# TK510_Kontakter.net
KiCad netlist of a schematic drawn in Altium Designer
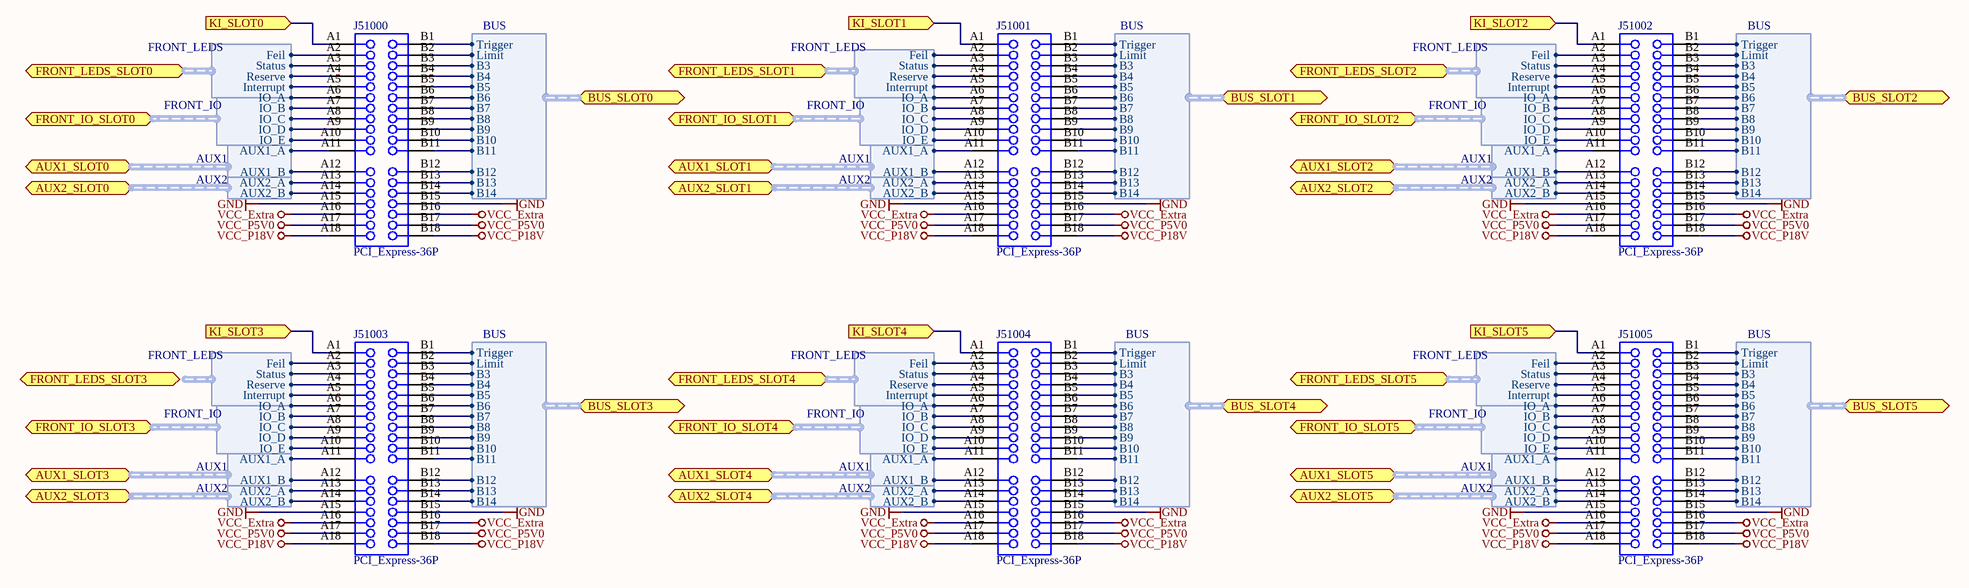
[diagram p0: TK510_Kontakter.SchDoc]

(export (version "E")
  (design (tool "Eeschema 10.0.6"))
  (components
    (comp (ref "J51000")
      (value "PCI_Express-36P")
      (footprint "PCI_Express-36P")
      (description "Board-to-Board Connector, PTH, Vertical, Pitch 1.00mm, 36-Position")
      (libsource (lib "OVLib") (part "PCI_Express-36P"))
    )
    (comp (ref "J51001")
      (value "PCI_Express-36P")
      (footprint "PCI_Express-36P")
      (description "Board-to-Board Connector, PTH, Vertical, Pitch 1.00mm, 36-Position")
      (libsource (lib "OVLib") (part "PCI_Express-36P"))
    )
    (comp (ref "J51002")
      (value "PCI_Express-36P")
      (footprint "PCI_Express-36P")
      (description "Board-to-Board Connector, PTH, Vertical, Pitch 1.00mm, 36-Position")
      (libsource (lib "OVLib") (part "PCI_Express-36P"))
    )
    (comp (ref "J51003")
      (value "PCI_Express-36P")
      (footprint "PCI_Express-36P")
      (description "Board-to-Board Connector, PTH, Vertical, Pitch 1.00mm, 36-Position")
      (libsource (lib "OVLib") (part "PCI_Express-36P"))
    )
    (comp (ref "J51004")
      (value "PCI_Express-36P")
      (footprint "PCI_Express-36P")
      (description "Board-to-Board Connector, PTH, Vertical, Pitch 1.00mm, 36-Position")
      (libsource (lib "OVLib") (part "PCI_Express-36P"))
    )
    (comp (ref "J51005")
      (value "PCI_Express-36P")
      (footprint "PCI_Express-36P")
      (description "Board-to-Board Connector, PTH, Vertical, Pitch 1.00mm, 36-Position")
      (libsource (lib "OVLib") (part "PCI_Express-36P"))
    )
  )
  (nets
    (net (code "21") (name "/KI_SLOT0") (class "Default")
      (node (ref "J51000") (pin "A1") (pinfunction "A1_A1") (pintype "passive"))
    )
    (net (code "22") (name "/KI_SLOT1") (class "Default")
      (node (ref "J51001") (pin "A1") (pinfunction "A1_A1") (pintype "passive"))
    )
    (net (code "23") (name "/KI_SLOT2") (class "Default")
      (node (ref "J51002") (pin "A1") (pinfunction "A1_A1") (pintype "passive"))
    )
    (net (code "24") (name "/KI_SLOT3") (class "Default")
      (node (ref "J51003") (pin "A1") (pinfunction "A1_A1") (pintype "passive"))
    )
    (net (code "25") (name "/KI_SLOT4") (class "Default")
      (node (ref "J51004") (pin "A1") (pinfunction "A1_A1") (pintype "passive"))
    )
    (net (code "26") (name "/KI_SLOT5") (class "Default")
      (node (ref "J51005") (pin "A1") (pinfunction "A1_A1") (pintype "passive"))
    )
    (net (code "29") (name "GND") (class "Default")
      (node (ref "J51000") (pin "A15") (pinfunction "A15_A15") (pintype "passive"))
      (node (ref "J51000") (pin "B15") (pinfunction "B15_B15") (pintype "passive"))
      (node (ref "J51001") (pin "A15") (pinfunction "A15_A15") (pintype "passive"))
      (node (ref "J51001") (pin "B15") (pinfunction "B15_B15") (pintype "passive"))
      (node (ref "J51002") (pin "A15") (pinfunction "A15_A15") (pintype "passive"))
      (node (ref "J51002") (pin "B15") (pinfunction "B15_B15") (pintype "passive"))
      (node (ref "J51003") (pin "A15") (pinfunction "A15_A15") (pintype "passive"))
      (node (ref "J51003") (pin "B15") (pinfunction "B15_B15") (pintype "passive"))
      (node (ref "J51004") (pin "A15") (pinfunction "A15_A15") (pintype "passive"))
      (node (ref "J51004") (pin "B15") (pinfunction "B15_B15") (pintype "passive"))
      (node (ref "J51005") (pin "A15") (pinfunction "A15_A15") (pintype "passive"))
      (node (ref "J51005") (pin "B15") (pinfunction "B15_B15") (pintype "passive"))
    )
    (net (code "30") (name "VCC_Extra") (class "Default")
      (node (ref "J51000") (pin "A16") (pinfunction "A16_A16") (pintype "passive"))
      (node (ref "J51000") (pin "B16") (pinfunction "B16_B16") (pintype "passive"))
      (node (ref "J51001") (pin "A16") (pinfunction "A16_A16") (pintype "passive"))
      (node (ref "J51001") (pin "B16") (pinfunction "B16_B16") (pintype "passive"))
      (node (ref "J51002") (pin "A16") (pinfunction "A16_A16") (pintype "passive"))
      (node (ref "J51002") (pin "B16") (pinfunction "B16_B16") (pintype "passive"))
      (node (ref "J51003") (pin "A16") (pinfunction "A16_A16") (pintype "passive"))
      (node (ref "J51003") (pin "B16") (pinfunction "B16_B16") (pintype "passive"))
      (node (ref "J51004") (pin "A16") (pinfunction "A16_A16") (pintype "passive"))
      (node (ref "J51004") (pin "B16") (pinfunction "B16_B16") (pintype "passive"))
      (node (ref "J51005") (pin "A16") (pinfunction "A16_A16") (pintype "passive"))
      (node (ref "J51005") (pin "B16") (pinfunction "B16_B16") (pintype "passive"))
    )
    (net (code "31") (name "VCC_P5V0") (class "Default")
      (node (ref "J51000") (pin "A17") (pinfunction "A17_A17") (pintype "passive"))
      (node (ref "J51000") (pin "B17") (pinfunction "B17_B17") (pintype "passive"))
      (node (ref "J51001") (pin "A17") (pinfunction "A17_A17") (pintype "passive"))
      (node (ref "J51001") (pin "B17") (pinfunction "B17_B17") (pintype "passive"))
      (node (ref "J51002") (pin "A17") (pinfunction "A17_A17") (pintype "passive"))
      (node (ref "J51002") (pin "B17") (pinfunction "B17_B17") (pintype "passive"))
      (node (ref "J51003") (pin "A17") (pinfunction "A17_A17") (pintype "passive"))
      (node (ref "J51003") (pin "B17") (pinfunction "B17_B17") (pintype "passive"))
      (node (ref "J51004") (pin "A17") (pinfunction "A17_A17") (pintype "passive"))
      (node (ref "J51004") (pin "B17") (pinfunction "B17_B17") (pintype "passive"))
      (node (ref "J51005") (pin "A17") (pinfunction "A17_A17") (pintype "passive"))
      (node (ref "J51005") (pin "B17") (pinfunction "B17_B17") (pintype "passive"))
    )
    (net (code "32") (name "VCC_P18V") (class "Default")
      (node (ref "J51000") (pin "A18") (pinfunction "A18_A18") (pintype "passive"))
      (node (ref "J51000") (pin "B18") (pinfunction "B18_B18") (pintype "passive"))
      (node (ref "J51001") (pin "A18") (pinfunction "A18_A18") (pintype "passive"))
      (node (ref "J51001") (pin "B18") (pinfunction "B18_B18") (pintype "passive"))
      (node (ref "J51002") (pin "A18") (pinfunction "A18_A18") (pintype "passive"))
      (node (ref "J51002") (pin "B18") (pinfunction "B18_B18") (pintype "passive"))
      (node (ref "J51003") (pin "A18") (pinfunction "A18_A18") (pintype "passive"))
      (node (ref "J51003") (pin "B18") (pinfunction "B18_B18") (pintype "passive"))
      (node (ref "J51004") (pin "A18") (pinfunction "A18_A18") (pintype "passive"))
      (node (ref "J51004") (pin "B18") (pinfunction "B18_B18") (pintype "passive"))
      (node (ref "J51005") (pin "A18") (pinfunction "A18_A18") (pintype "passive"))
      (node (ref "J51005") (pin "B18") (pinfunction "B18_B18") (pintype "passive"))
    )
    (net (code "33") (name "unconnected-(J51000-PadA2)") (class "Default")
      (node (ref "J51000") (pin "A2") (pinfunction "A2_A2") (pintype "passive"))
    )
    (net (code "34") (name "unconnected-(J51000-PadA3)") (class "Default")
      (node (ref "J51000") (pin "A3") (pinfunction "A3_A3") (pintype "passive"))
    )
    (net (code "35") (name "unconnected-(J51000-PadA4)") (class "Default")
      (node (ref "J51000") (pin "A4") (pinfunction "A4_A4") (pintype "passive"))
    )
    (net (code "36") (name "unconnected-(J51000-PadA5)") (class "Default")
      (node (ref "J51000") (pin "A5") (pinfunction "A5_A5") (pintype "passive"))
    )
    (net (code "37") (name "unconnected-(J51000-PadA6)") (class "Default")
      (node (ref "J51000") (pin "A6") (pinfunction "A6_A6") (pintype "passive"))
    )
    (net (code "38") (name "unconnected-(J51000-PadA7)") (class "Default")
      (node (ref "J51000") (pin "A7") (pinfunction "A7_A7") (pintype "passive"))
    )
    (net (code "39") (name "unconnected-(J51000-PadA8)") (class "Default")
      (node (ref "J51000") (pin "A8") (pinfunction "A8_A8") (pintype "passive"))
    )
    (net (code "40") (name "unconnected-(J51000-PadA9)") (class "Default")
      (node (ref "J51000") (pin "A9") (pinfunction "A9_A9") (pintype "passive"))
    )
    (net (code "41") (name "unconnected-(J51000-PadA10)") (class "Default")
      (node (ref "J51000") (pin "A10") (pinfunction "A10_A10") (pintype "passive"))
    )
    (net (code "42") (name "unconnected-(J51000-PadA11)") (class "Default")
      (node (ref "J51000") (pin "A11") (pinfunction "A11_A11") (pintype "passive"))
    )
    (net (code "43") (name "unconnected-(J51000-PadA12)") (class "Default")
      (node (ref "J51000") (pin "A12") (pinfunction "A12_A12") (pintype "passive"))
    )
    (net (code "44") (name "unconnected-(J51000-PadA13)") (class "Default")
      (node (ref "J51000") (pin "A13") (pinfunction "A13_A13") (pintype "passive"))
    )
    (net (code "45") (name "unconnected-(J51000-PadA14)") (class "Default")
      (node (ref "J51000") (pin "A14") (pinfunction "A14_A14") (pintype "passive"))
    )
    (net (code "46") (name "unconnected-(J51000-PadB1)") (class "Default")
      (node (ref "J51000") (pin "B1") (pinfunction "B1_B1") (pintype "passive"))
    )
    (net (code "47") (name "unconnected-(J51000-PadB2)") (class "Default")
      (node (ref "J51000") (pin "B2") (pinfunction "B2_B2") (pintype "passive"))
    )
    (net (code "48") (name "unconnected-(J51000-PadB3)") (class "Default")
      (node (ref "J51000") (pin "B3") (pinfunction "B3_B3") (pintype "passive"))
    )
    (net (code "49") (name "unconnected-(J51000-PadB4)") (class "Default")
      (node (ref "J51000") (pin "B4") (pinfunction "B4_B4") (pintype "passive"))
    )
    (net (code "50") (name "unconnected-(J51000-PadB5)") (class "Default")
      (node (ref "J51000") (pin "B5") (pinfunction "B5_B5") (pintype "passive"))
    )
    (net (code "51") (name "unconnected-(J51000-PadB6)") (class "Default")
      (node (ref "J51000") (pin "B6") (pinfunction "B6_B6") (pintype "passive"))
    )
    (net (code "52") (name "unconnected-(J51000-PadB7)") (class "Default")
      (node (ref "J51000") (pin "B7") (pinfunction "B7_B7") (pintype "passive"))
    )
    (net (code "53") (name "unconnected-(J51000-PadB8)") (class "Default")
      (node (ref "J51000") (pin "B8") (pinfunction "B8_B8") (pintype "passive"))
    )
    (net (code "54") (name "unconnected-(J51000-PadB9)") (class "Default")
      (node (ref "J51000") (pin "B9") (pinfunction "B9_B9") (pintype "passive"))
    )
    (net (code "55") (name "unconnected-(J51000-PadB10)") (class "Default")
      (node (ref "J51000") (pin "B10") (pinfunction "B10_B10") (pintype "passive"))
    )
    (net (code "56") (name "unconnected-(J51000-PadB11)") (class "Default")
      (node (ref "J51000") (pin "B11") (pinfunction "B11_B11") (pintype "passive"))
    )
    (net (code "57") (name "unconnected-(J51000-PadB12)") (class "Default")
      (node (ref "J51000") (pin "B12") (pinfunction "B12_B12") (pintype "passive"))
    )
    (net (code "58") (name "unconnected-(J51000-PadB13)") (class "Default")
      (node (ref "J51000") (pin "B13") (pinfunction "B13_B13") (pintype "passive"))
    )
    (net (code "59") (name "unconnected-(J51000-PadB14)") (class "Default")
      (node (ref "J51000") (pin "B14") (pinfunction "B14_B14") (pintype "passive"))
    )
    (net (code "60") (name "unconnected-(J51001-PadA2)") (class "Default")
      (node (ref "J51001") (pin "A2") (pinfunction "A2_A2") (pintype "passive"))
    )
    (net (code "61") (name "unconnected-(J51001-PadA3)") (class "Default")
      (node (ref "J51001") (pin "A3") (pinfunction "A3_A3") (pintype "passive"))
    )
    (net (code "62") (name "unconnected-(J51001-PadA4)") (class "Default")
      (node (ref "J51001") (pin "A4") (pinfunction "A4_A4") (pintype "passive"))
    )
    (net (code "63") (name "unconnected-(J51001-PadA5)") (class "Default")
      (node (ref "J51001") (pin "A5") (pinfunction "A5_A5") (pintype "passive"))
    )
    (net (code "64") (name "unconnected-(J51001-PadA6)") (class "Default")
      (node (ref "J51001") (pin "A6") (pinfunction "A6_A6") (pintype "passive"))
    )
    (net (code "65") (name "unconnected-(J51001-PadA7)") (class "Default")
      (node (ref "J51001") (pin "A7") (pinfunction "A7_A7") (pintype "passive"))
    )
    (net (code "66") (name "unconnected-(J51001-PadA8)") (class "Default")
      (node (ref "J51001") (pin "A8") (pinfunction "A8_A8") (pintype "passive"))
    )
    (net (code "67") (name "unconnected-(J51001-PadA9)") (class "Default")
      (node (ref "J51001") (pin "A9") (pinfunction "A9_A9") (pintype "passive"))
    )
    (net (code "68") (name "unconnected-(J51001-PadA10)") (class "Default")
      (node (ref "J51001") (pin "A10") (pinfunction "A10_A10") (pintype "passive"))
    )
    (net (code "69") (name "unconnected-(J51001-PadA11)") (class "Default")
      (node (ref "J51001") (pin "A11") (pinfunction "A11_A11") (pintype "passive"))
    )
    (net (code "70") (name "unconnected-(J51001-PadA12)") (class "Default")
      (node (ref "J51001") (pin "A12") (pinfunction "A12_A12") (pintype "passive"))
    )
    (net (code "71") (name "unconnected-(J51001-PadA13)") (class "Default")
      (node (ref "J51001") (pin "A13") (pinfunction "A13_A13") (pintype "passive"))
    )
    (net (code "72") (name "unconnected-(J51001-PadA14)") (class "Default")
      (node (ref "J51001") (pin "A14") (pinfunction "A14_A14") (pintype "passive"))
    )
    (net (code "73") (name "unconnected-(J51001-PadB1)") (class "Default")
      (node (ref "J51001") (pin "B1") (pinfunction "B1_B1") (pintype "passive"))
    )
    (net (code "74") (name "unconnected-(J51001-PadB2)") (class "Default")
      (node (ref "J51001") (pin "B2") (pinfunction "B2_B2") (pintype "passive"))
    )
    (net (code "75") (name "unconnected-(J51001-PadB3)") (class "Default")
      (node (ref "J51001") (pin "B3") (pinfunction "B3_B3") (pintype "passive"))
    )
    (net (code "76") (name "unconnected-(J51001-PadB4)") (class "Default")
      (node (ref "J51001") (pin "B4") (pinfunction "B4_B4") (pintype "passive"))
    )
    (net (code "77") (name "unconnected-(J51001-PadB5)") (class "Default")
      (node (ref "J51001") (pin "B5") (pinfunction "B5_B5") (pintype "passive"))
    )
    (net (code "78") (name "unconnected-(J51001-PadB6)") (class "Default")
      (node (ref "J51001") (pin "B6") (pinfunction "B6_B6") (pintype "passive"))
    )
    (net (code "79") (name "unconnected-(J51001-PadB7)") (class "Default")
      (node (ref "J51001") (pin "B7") (pinfunction "B7_B7") (pintype "passive"))
    )
    (net (code "80") (name "unconnected-(J51001-PadB8)") (class "Default")
      (node (ref "J51001") (pin "B8") (pinfunction "B8_B8") (pintype "passive"))
    )
    (net (code "81") (name "unconnected-(J51001-PadB9)") (class "Default")
      (node (ref "J51001") (pin "B9") (pinfunction "B9_B9") (pintype "passive"))
    )
    (net (code "82") (name "unconnected-(J51001-PadB10)") (class "Default")
      (node (ref "J51001") (pin "B10") (pinfunction "B10_B10") (pintype "passive"))
    )
    (net (code "83") (name "unconnected-(J51001-PadB11)") (class "Default")
      (node (ref "J51001") (pin "B11") (pinfunction "B11_B11") (pintype "passive"))
    )
    (net (code "84") (name "unconnected-(J51001-PadB12)") (class "Default")
      (node (ref "J51001") (pin "B12") (pinfunction "B12_B12") (pintype "passive"))
    )
    (net (code "85") (name "unconnected-(J51001-PadB13)") (class "Default")
      (node (ref "J51001") (pin "B13") (pinfunction "B13_B13") (pintype "passive"))
    )
    (net (code "86") (name "unconnected-(J51001-PadB14)") (class "Default")
      (node (ref "J51001") (pin "B14") (pinfunction "B14_B14") (pintype "passive"))
    )
    (net (code "87") (name "unconnected-(J51002-PadA2)") (class "Default")
      (node (ref "J51002") (pin "A2") (pinfunction "A2_A2") (pintype "passive"))
    )
    (net (code "88") (name "unconnected-(J51002-PadA3)") (class "Default")
      (node (ref "J51002") (pin "A3") (pinfunction "A3_A3") (pintype "passive"))
    )
    (net (code "89") (name "unconnected-(J51002-PadA4)") (class "Default")
      (node (ref "J51002") (pin "A4") (pinfunction "A4_A4") (pintype "passive"))
    )
    (net (code "90") (name "unconnected-(J51002-PadA5)") (class "Default")
      (node (ref "J51002") (pin "A5") (pinfunction "A5_A5") (pintype "passive"))
    )
    (net (code "91") (name "unconnected-(J51002-PadA6)") (class "Default")
      (node (ref "J51002") (pin "A6") (pinfunction "A6_A6") (pintype "passive"))
    )
    (net (code "92") (name "unconnected-(J51002-PadA7)") (class "Default")
      (node (ref "J51002") (pin "A7") (pinfunction "A7_A7") (pintype "passive"))
    )
    (net (code "93") (name "unconnected-(J51002-PadA8)") (class "Default")
      (node (ref "J51002") (pin "A8") (pinfunction "A8_A8") (pintype "passive"))
    )
    (net (code "94") (name "unconnected-(J51002-PadA9)") (class "Default")
      (node (ref "J51002") (pin "A9") (pinfunction "A9_A9") (pintype "passive"))
    )
    (net (code "95") (name "unconnected-(J51002-PadA10)") (class "Default")
      (node (ref "J51002") (pin "A10") (pinfunction "A10_A10") (pintype "passive"))
    )
    (net (code "96") (name "unconnected-(J51002-PadA11)") (class "Default")
      (node (ref "J51002") (pin "A11") (pinfunction "A11_A11") (pintype "passive"))
    )
    (net (code "97") (name "unconnected-(J51002-PadA12)") (class "Default")
      (node (ref "J51002") (pin "A12") (pinfunction "A12_A12") (pintype "passive"))
    )
    (net (code "98") (name "unconnected-(J51002-PadA13)") (class "Default")
      (node (ref "J51002") (pin "A13") (pinfunction "A13_A13") (pintype "passive"))
    )
    (net (code "99") (name "unconnected-(J51002-PadA14)") (class "Default")
      (node (ref "J51002") (pin "A14") (pinfunction "A14_A14") (pintype "passive"))
    )
    (net (code "100") (name "unconnected-(J51002-PadB1)") (class "Default")
      (node (ref "J51002") (pin "B1") (pinfunction "B1_B1") (pintype "passive"))
    )
    (net (code "101") (name "unconnected-(J51002-PadB2)") (class "Default")
      (node (ref "J51002") (pin "B2") (pinfunction "B2_B2") (pintype "passive"))
    )
    (net (code "102") (name "unconnected-(J51002-PadB3)") (class "Default")
      (node (ref "J51002") (pin "B3") (pinfunction "B3_B3") (pintype "passive"))
    )
    (net (code "103") (name "unconnected-(J51002-PadB4)") (class "Default")
      (node (ref "J51002") (pin "B4") (pinfunction "B4_B4") (pintype "passive"))
    )
    (net (code "104") (name "unconnected-(J51002-PadB5)") (class "Default")
      (node (ref "J51002") (pin "B5") (pinfunction "B5_B5") (pintype "passive"))
    )
    (net (code "105") (name "unconnected-(J51002-PadB6)") (class "Default")
      (node (ref "J51002") (pin "B6") (pinfunction "B6_B6") (pintype "passive"))
    )
    (net (code "106") (name "unconnected-(J51002-PadB7)") (class "Default")
      (node (ref "J51002") (pin "B7") (pinfunction "B7_B7") (pintype "passive"))
    )
    (net (code "107") (name "unconnected-(J51002-PadB8)") (class "Default")
      (node (ref "J51002") (pin "B8") (pinfunction "B8_B8") (pintype "passive"))
    )
    (net (code "108") (name "unconnected-(J51002-PadB9)") (class "Default")
      (node (ref "J51002") (pin "B9") (pinfunction "B9_B9") (pintype "passive"))
    )
    (net (code "109") (name "unconnected-(J51002-PadB10)") (class "Default")
      (node (ref "J51002") (pin "B10") (pinfunction "B10_B10") (pintype "passive"))
    )
    (net (code "110") (name "unconnected-(J51002-PadB11)") (class "Default")
      (node (ref "J51002") (pin "B11") (pinfunction "B11_B11") (pintype "passive"))
    )
    (net (code "111") (name "unconnected-(J51002-PadB12)") (class "Default")
      (node (ref "J51002") (pin "B12") (pinfunction "B12_B12") (pintype "passive"))
    )
    (net (code "112") (name "unconnected-(J51002-PadB13)") (class "Default")
      (node (ref "J51002") (pin "B13") (pinfunction "B13_B13") (pintype "passive"))
    )
    (net (code "113") (name "unconnected-(J51002-PadB14)") (class "Default")
      (node (ref "J51002") (pin "B14") (pinfunction "B14_B14") (pintype "passive"))
    )
    (net (code "114") (name "unconnected-(J51003-PadA2)") (class "Default")
      (node (ref "J51003") (pin "A2") (pinfunction "A2_A2") (pintype "passive"))
    )
    (net (code "115") (name "unconnected-(J51003-PadA3)") (class "Default")
      (node (ref "J51003") (pin "A3") (pinfunction "A3_A3") (pintype "passive"))
    )
    (net (code "116") (name "unconnected-(J51003-PadA4)") (class "Default")
      (node (ref "J51003") (pin "A4") (pinfunction "A4_A4") (pintype "passive"))
    )
    (net (code "117") (name "unconnected-(J51003-PadA5)") (class "Default")
      (node (ref "J51003") (pin "A5") (pinfunction "A5_A5") (pintype "passive"))
    )
    (net (code "118") (name "unconnected-(J51003-PadA6)") (class "Default")
      (node (ref "J51003") (pin "A6") (pinfunction "A6_A6") (pintype "passive"))
    )
    (net (code "119") (name "unconnected-(J51003-PadA7)") (class "Default")
      (node (ref "J51003") (pin "A7") (pinfunction "A7_A7") (pintype "passive"))
    )
    (net (code "120") (name "unconnected-(J51003-PadA8)") (class "Default")
      (node (ref "J51003") (pin "A8") (pinfunction "A8_A8") (pintype "passive"))
    )
    (net (code "121") (name "unconnected-(J51003-PadA9)") (class "Default")
      (node (ref "J51003") (pin "A9") (pinfunction "A9_A9") (pintype "passive"))
    )
    (net (code "122") (name "unconnected-(J51003-PadA10)") (class "Default")
      (node (ref "J51003") (pin "A10") (pinfunction "A10_A10") (pintype "passive"))
    )
    (net (code "123") (name "unconnected-(J51003-PadA11)") (class "Default")
      (node (ref "J51003") (pin "A11") (pinfunction "A11_A11") (pintype "passive"))
    )
    (net (code "124") (name "unconnected-(J51003-PadA12)") (class "Default")
      (node (ref "J51003") (pin "A12") (pinfunction "A12_A12") (pintype "passive"))
    )
    (net (code "125") (name "unconnected-(J51003-PadA13)") (class "Default")
      (node (ref "J51003") (pin "A13") (pinfunction "A13_A13") (pintype "passive"))
    )
    (net (code "126") (name "unconnected-(J51003-PadA14)") (class "Default")
      (node (ref "J51003") (pin "A14") (pinfunction "A14_A14") (pintype "passive"))
    )
    (net (code "127") (name "unconnected-(J51003-PadB1)") (class "Default")
      (node (ref "J51003") (pin "B1") (pinfunction "B1_B1") (pintype "passive"))
    )
    (net (code "128") (name "unconnected-(J51003-PadB2)") (class "Default")
      (node (ref "J51003") (pin "B2") (pinfunction "B2_B2") (pintype "passive"))
    )
    (net (code "129") (name "unconnected-(J51003-PadB3)") (class "Default")
      (node (ref "J51003") (pin "B3") (pinfunction "B3_B3") (pintype "passive"))
    )
    (net (code "130") (name "unconnected-(J51003-PadB4)") (class "Default")
      (node (ref "J51003") (pin "B4") (pinfunction "B4_B4") (pintype "passive"))
    )
    (net (code "131") (name "unconnected-(J51003-PadB5)") (class "Default")
      (node (ref "J51003") (pin "B5") (pinfunction "B5_B5") (pintype "passive"))
    )
    (net (code "132") (name "unconnected-(J51003-PadB6)") (class "Default")
      (node (ref "J51003") (pin "B6") (pinfunction "B6_B6") (pintype "passive"))
    )
    (net (code "133") (name "unconnected-(J51003-PadB7)") (class "Default")
      (node (ref "J51003") (pin "B7") (pinfunction "B7_B7") (pintype "passive"))
    )
    (net (code "134") (name "unconnected-(J51003-PadB8)") (class "Default")
      (node (ref "J51003") (pin "B8") (pinfunction "B8_B8") (pintype "passive"))
    )
    (net (code "135") (name "unconnected-(J51003-PadB9)") (class "Default")
      (node (ref "J51003") (pin "B9") (pinfunction "B9_B9") (pintype "passive"))
    )
    (net (code "136") (name "unconnected-(J51003-PadB10)") (class "Default")
      (node (ref "J51003") (pin "B10") (pinfunction "B10_B10") (pintype "passive"))
    )
    (net (code "137") (name "unconnected-(J51003-PadB11)") (class "Default")
      (node (ref "J51003") (pin "B11") (pinfunction "B11_B11") (pintype "passive"))
    )
    (net (code "138") (name "unconnected-(J51003-PadB12)") (class "Default")
      (node (ref "J51003") (pin "B12") (pinfunction "B12_B12") (pintype "passive"))
    )
    (net (code "139") (name "unconnected-(J51003-PadB13)") (class "Default")
      (node (ref "J51003") (pin "B13") (pinfunction "B13_B13") (pintype "passive"))
    )
    (net (code "140") (name "unconnected-(J51003-PadB14)") (class "Default")
      (node (ref "J51003") (pin "B14") (pinfunction "B14_B14") (pintype "passive"))
    )
    (net (code "141") (name "unconnected-(J51004-PadA2)") (class "Default")
      (node (ref "J51004") (pin "A2") (pinfunction "A2_A2") (pintype "passive"))
    )
    (net (code "142") (name "unconnected-(J51004-PadA3)") (class "Default")
      (node (ref "J51004") (pin "A3") (pinfunction "A3_A3") (pintype "passive"))
    )
    (net (code "143") (name "unconnected-(J51004-PadA4)") (class "Default")
      (node (ref "J51004") (pin "A4") (pinfunction "A4_A4") (pintype "passive"))
    )
    (net (code "144") (name "unconnected-(J51004-PadA5)") (class "Default")
      (node (ref "J51004") (pin "A5") (pinfunction "A5_A5") (pintype "passive"))
    )
    (net (code "145") (name "unconnected-(J51004-PadA6)") (class "Default")
      (node (ref "J51004") (pin "A6") (pinfunction "A6_A6") (pintype "passive"))
    )
    (net (code "146") (name "unconnected-(J51004-PadA7)") (class "Default")
      (node (ref "J51004") (pin "A7") (pinfunction "A7_A7") (pintype "passive"))
    )
    (net (code "147") (name "unconnected-(J51004-PadA8)") (class "Default")
      (node (ref "J51004") (pin "A8") (pinfunction "A8_A8") (pintype "passive"))
    )
    (net (code "148") (name "unconnected-(J51004-PadA9)") (class "Default")
      (node (ref "J51004") (pin "A9") (pinfunction "A9_A9") (pintype "passive"))
    )
    (net (code "149") (name "unconnected-(J51004-PadA10)") (class "Default")
      (node (ref "J51004") (pin "A10") (pinfunction "A10_A10") (pintype "passive"))
    )
    (net (code "150") (name "unconnected-(J51004-PadA11)") (class "Default")
      (node (ref "J51004") (pin "A11") (pinfunction "A11_A11") (pintype "passive"))
    )
    (net (code "151") (name "unconnected-(J51004-PadA12)") (class "Default")
      (node (ref "J51004") (pin "A12") (pinfunction "A12_A12") (pintype "passive"))
    )
    (net (code "152") (name "unconnected-(J51004-PadA13)") (class "Default")
      (node (ref "J51004") (pin "A13") (pinfunction "A13_A13") (pintype "passive"))
    )
    (net (code "153") (name "unconnected-(J51004-PadA14)") (class "Default")
      (node (ref "J51004") (pin "A14") (pinfunction "A14_A14") (pintype "passive"))
    )
    (net (code "154") (name "unconnected-(J51004-PadB1)") (class "Default")
      (node (ref "J51004") (pin "B1") (pinfunction "B1_B1") (pintype "passive"))
    )
    (net (code "155") (name "unconnected-(J51004-PadB2)") (class "Default")
      (node (ref "J51004") (pin "B2") (pinfunction "B2_B2") (pintype "passive"))
    )
    (net (code "156") (name "unconnected-(J51004-PadB3)") (class "Default")
      (node (ref "J51004") (pin "B3") (pinfunction "B3_B3") (pintype "passive"))
    )
    (net (code "157") (name "unconnected-(J51004-PadB4)") (class "Default")
      (node (ref "J51004") (pin "B4") (pinfunction "B4_B4") (pintype "passive"))
    )
    (net (code "158") (name "unconnected-(J51004-PadB5)") (class "Default")
      (node (ref "J51004") (pin "B5") (pinfunction "B5_B5") (pintype "passive"))
    )
    (net (code "159") (name "unconnected-(J51004-PadB6)") (class "Default")
      (node (ref "J51004") (pin "B6") (pinfunction "B6_B6") (pintype "passive"))
    )
    (net (code "160") (name "unconnected-(J51004-PadB7)") (class "Default")
      (node (ref "J51004") (pin "B7") (pinfunction "B7_B7") (pintype "passive"))
    )
    (net (code "161") (name "unconnected-(J51004-PadB8)") (class "Default")
      (node (ref "J51004") (pin "B8") (pinfunction "B8_B8") (pintype "passive"))
    )
    (net (code "162") (name "unconnected-(J51004-PadB9)") (class "Default")
      (node (ref "J51004") (pin "B9") (pinfunction "B9_B9") (pintype "passive"))
    )
    (net (code "163") (name "unconnected-(J51004-PadB10)") (class "Default")
      (node (ref "J51004") (pin "B10") (pinfunction "B10_B10") (pintype "passive"))
    )
    (net (code "164") (name "unconnected-(J51004-PadB11)") (class "Default")
      (node (ref "J51004") (pin "B11") (pinfunction "B11_B11") (pintype "passive"))
    )
    (net (code "165") (name "unconnected-(J51004-PadB12)") (class "Default")
      (node (ref "J51004") (pin "B12") (pinfunction "B12_B12") (pintype "passive"))
    )
    (net (code "166") (name "unconnected-(J51004-PadB13)") (class "Default")
      (node (ref "J51004") (pin "B13") (pinfunction "B13_B13") (pintype "passive"))
    )
    (net (code "167") (name "unconnected-(J51004-PadB14)") (class "Default")
      (node (ref "J51004") (pin "B14") (pinfunction "B14_B14") (pintype "passive"))
    )
    (net (code "168") (name "unconnected-(J51005-PadA2)") (class "Default")
      (node (ref "J51005") (pin "A2") (pinfunction "A2_A2") (pintype "passive"))
    )
    (net (code "169") (name "unconnected-(J51005-PadA3)") (class "Default")
      (node (ref "J51005") (pin "A3") (pinfunction "A3_A3") (pintype "passive"))
    )
    (net (code "170") (name "unconnected-(J51005-PadA4)") (class "Default")
      (node (ref "J51005") (pin "A4") (pinfunction "A4_A4") (pintype "passive"))
    )
    (net (code "171") (name "unconnected-(J51005-PadA5)") (class "Default")
      (node (ref "J51005") (pin "A5") (pinfunction "A5_A5") (pintype "passive"))
    )
    (net (code "172") (name "unconnected-(J51005-PadA6)") (class "Default")
      (node (ref "J51005") (pin "A6") (pinfunction "A6_A6") (pintype "passive"))
    )
    (net (code "173") (name "unconnected-(J51005-PadA7)") (class "Default")
      (node (ref "J51005") (pin "A7") (pinfunction "A7_A7") (pintype "passive"))
    )
    (net (code "174") (name "unconnected-(J51005-PadA8)") (class "Default")
      (node (ref "J51005") (pin "A8") (pinfunction "A8_A8") (pintype "passive"))
    )
    (net (code "175") (name "unconnected-(J51005-PadA9)") (class "Default")
      (node (ref "J51005") (pin "A9") (pinfunction "A9_A9") (pintype "passive"))
    )
    (net (code "176") (name "unconnected-(J51005-PadA10)") (class "Default")
      (node (ref "J51005") (pin "A10") (pinfunction "A10_A10") (pintype "passive"))
    )
    (net (code "177") (name "unconnected-(J51005-PadA11)") (class "Default")
      (node (ref "J51005") (pin "A11") (pinfunction "A11_A11") (pintype "passive"))
    )
    (net (code "178") (name "unconnected-(J51005-PadA12)") (class "Default")
      (node (ref "J51005") (pin "A12") (pinfunction "A12_A12") (pintype "passive"))
    )
    (net (code "179") (name "unconnected-(J51005-PadA13)") (class "Default")
      (node (ref "J51005") (pin "A13") (pinfunction "A13_A13") (pintype "passive"))
    )
    (net (code "180") (name "unconnected-(J51005-PadA14)") (class "Default")
      (node (ref "J51005") (pin "A14") (pinfunction "A14_A14") (pintype "passive"))
    )
    (net (code "181") (name "unconnected-(J51005-PadB1)") (class "Default")
      (node (ref "J51005") (pin "B1") (pinfunction "B1_B1") (pintype "passive"))
    )
    (net (code "182") (name "unconnected-(J51005-PadB2)") (class "Default")
      (node (ref "J51005") (pin "B2") (pinfunction "B2_B2") (pintype "passive"))
    )
    (net (code "183") (name "unconnected-(J51005-PadB3)") (class "Default")
      (node (ref "J51005") (pin "B3") (pinfunction "B3_B3") (pintype "passive"))
    )
    (net (code "184") (name "unconnected-(J51005-PadB4)") (class "Default")
      (node (ref "J51005") (pin "B4") (pinfunction "B4_B4") (pintype "passive"))
    )
    (net (code "185") (name "unconnected-(J51005-PadB5)") (class "Default")
      (node (ref "J51005") (pin "B5") (pinfunction "B5_B5") (pintype "passive"))
    )
    (net (code "186") (name "unconnected-(J51005-PadB6)") (class "Default")
      (node (ref "J51005") (pin "B6") (pinfunction "B6_B6") (pintype "passive"))
    )
    (net (code "187") (name "unconnected-(J51005-PadB7)") (class "Default")
      (node (ref "J51005") (pin "B7") (pinfunction "B7_B7") (pintype "passive"))
    )
    (net (code "188") (name "unconnected-(J51005-PadB8)") (class "Default")
      (node (ref "J51005") (pin "B8") (pinfunction "B8_B8") (pintype "passive"))
    )
    (net (code "189") (name "unconnected-(J51005-PadB9)") (class "Default")
      (node (ref "J51005") (pin "B9") (pinfunction "B9_B9") (pintype "passive"))
    )
    (net (code "190") (name "unconnected-(J51005-PadB10)") (class "Default")
      (node (ref "J51005") (pin "B10") (pinfunction "B10_B10") (pintype "passive"))
    )
    (net (code "191") (name "unconnected-(J51005-PadB11)") (class "Default")
      (node (ref "J51005") (pin "B11") (pinfunction "B11_B11") (pintype "passive"))
    )
    (net (code "192") (name "unconnected-(J51005-PadB12)") (class "Default")
      (node (ref "J51005") (pin "B12") (pinfunction "B12_B12") (pintype "passive"))
    )
    (net (code "193") (name "unconnected-(J51005-PadB13)") (class "Default")
      (node (ref "J51005") (pin "B13") (pinfunction "B13_B13") (pintype "passive"))
    )
    (net (code "194") (name "unconnected-(J51005-PadB14)") (class "Default")
      (node (ref "J51005") (pin "B14") (pinfunction "B14_B14") (pintype "passive"))
    )
  )
)
